# ATXDistributorBoard_ATM.net
KiCad netlist of a schematic drawn in EAGLE
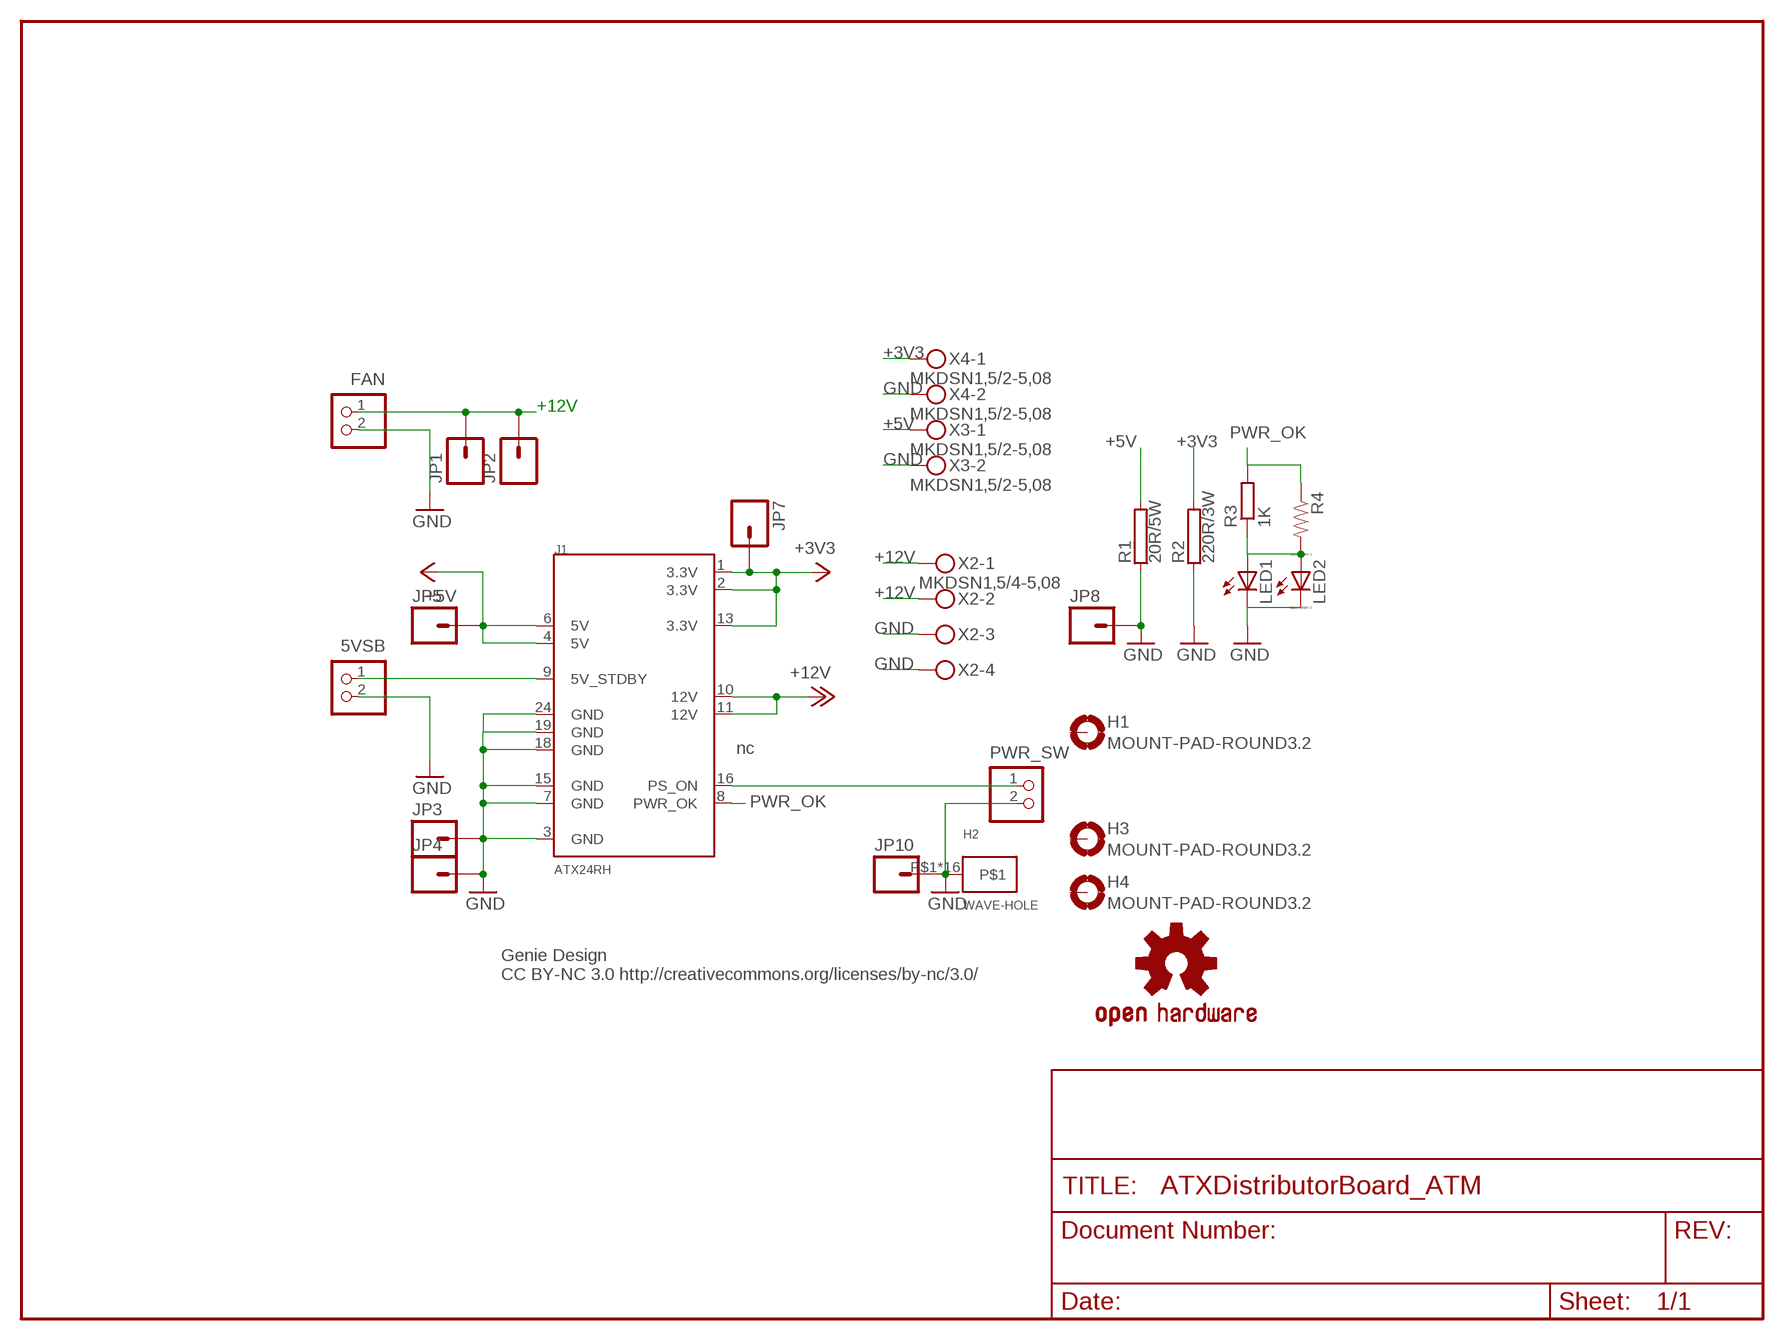
[diagram p0: schematic, sheet 1]

(export (version "E")
  (design (tool "Eeschema 10.0.6"))
  (components
    (comp (ref "5VSB")
      (value "B2B-XH-A")
      (footprint "eagle-import:B2B-XH-A")
      (libsource (lib "eagle-import") (part "B2B-XH-A"))
    )
    (comp (ref "FAN")
      (value "B2B-XH-A")
      (footprint "eagle-import:B2B-XH-A")
      (libsource (lib "eagle-import") (part "B2B-XH-A"))
    )
    (comp (ref "H1")
      (value "MOUNT-PAD-ROUND3.2")
      (footprint "eagle-import:3,2-PAD")
      (libsource (lib "eagle-import") (part "MOUNT-PAD-ROUND3.2"))
    )
    (comp (ref "H2")
      (value "WAVE-HOLE")
      (footprint "eagle-import:3,0-WAVE-HOLE")
      (libsource (lib "eagle-import") (part "WAVE-HOLE"))
    )
    (comp (ref "H3")
      (value "MOUNT-PAD-ROUND3.2")
      (footprint "eagle-import:3,2-PAD")
      (libsource (lib "eagle-import") (part "MOUNT-PAD-ROUND3.2"))
    )
    (comp (ref "H4")
      (value "MOUNT-PAD-ROUND3.2")
      (footprint "eagle-import:3,2-PAD")
      (libsource (lib "eagle-import") (part "MOUNT-PAD-ROUND3.2"))
    )
    (comp (ref "J1")
      (value "ATX24RH")
      (footprint "eagle-import:ATX24_RIGHT_ANGLE")
      (libsource (lib "eagle-import") (part "ATX24RH"))
    )
    (comp (ref "JP1")
      (value "M01PTH_NO_SILK_YES_STOP")
      (footprint "eagle-import:1X01_NO_SILK")
      (libsource (lib "eagle-import") (part "M01PTH_NO_SILK_YES_STOP"))
    )
    (comp (ref "JP2")
      (value "M01PTH_NO_SILK_YES_STOP")
      (footprint "eagle-import:1X01_NO_SILK")
      (libsource (lib "eagle-import") (part "M01PTH_NO_SILK_YES_STOP"))
    )
    (comp (ref "JP3")
      (value "M01PTH_NO_SILK_YES_STOP")
      (footprint "eagle-import:1X01_NO_SILK")
      (libsource (lib "eagle-import") (part "M01PTH_NO_SILK_YES_STOP"))
    )
    (comp (ref "JP4")
      (value "M01PTH_NO_SILK_YES_STOP")
      (footprint "eagle-import:1X01_NO_SILK")
      (libsource (lib "eagle-import") (part "M01PTH_NO_SILK_YES_STOP"))
    )
    (comp (ref "JP5")
      (value "M01PTH_NO_SILK_YES_STOP")
      (footprint "eagle-import:1X01_NO_SILK")
      (libsource (lib "eagle-import") (part "M01PTH_NO_SILK_YES_STOP"))
    )
    (comp (ref "JP7")
      (value "M01PTH_NO_SILK_YES_STOP")
      (footprint "eagle-import:1X01_NO_SILK")
      (libsource (lib "eagle-import") (part "M01PTH_NO_SILK_YES_STOP"))
    )
    (comp (ref "JP8")
      (value "M01PTH_NO_SILK_YES_STOP")
      (footprint "eagle-import:1X01_NO_SILK")
      (libsource (lib "eagle-import") (part "M01PTH_NO_SILK_YES_STOP"))
    )
    (comp (ref "JP10")
      (value "M01PTH_NO_SILK_YES_STOP")
      (footprint "eagle-import:1X01_NO_SILK")
      (libsource (lib "eagle-import") (part "M01PTH_NO_SILK_YES_STOP"))
    )
    (comp (ref "LED1")
      (value "LED3MM")
      (footprint "eagle-import:LED3MM")
      (libsource (lib "eagle-import") (part "LED3MM"))
    )
    (comp (ref "LED2")
      (value "LED_ESML0603")
      (footprint "eagle-import:LED_SML0603")
      (libsource (lib "eagle-import") (part "LED_ESML0603"))
    )
    (comp (ref "LOGO1")
      (value "OSHW-LOGOS-COPPER")
      (footprint "eagle-import:OSHW-LOGO-S_COPPER")
      (libsource (lib "eagle-import") (part "OSHW-LOGOS-COPPER"))
    )
    (comp (ref "PWR_SW")
      (value "B2B-XH-A")
      (footprint "eagle-import:B2B-XH-A")
      (libsource (lib "eagle-import") (part "B2B-XH-A"))
    )
    (comp (ref "R1")
      (value "20R/5W")
      (footprint "eagle-import:HPS923")
      (libsource (lib "eagle-import") (part "RHPS923"))
    )
    (comp (ref "R2")
      (value "220R/3W")
      (footprint "eagle-import:CA4050")
      (libsource (lib "eagle-import") (part "RCA4050"))
    )
    (comp (ref "R3")
      (value "1K")
      (footprint "eagle-import:0207_10")
      (libsource (lib "eagle-import") (part "R-EU_0207/10"))
    )
    (comp (ref "R4")
      (value "RESISTOR0603-RES")
      (footprint "eagle-import:0603-RES")
      (libsource (lib "eagle-import") (part "RESISTOR0603-RES"))
    )
    (comp (ref "X2")
      (value "MKDSN1,5/4-5,08")
      (footprint "eagle-import:MKDSN1,5_4-5,08")
      (fields (field (name "MPN") "SMKDSN1,5/4-5,08"))
      (libsource (lib "eagle-import") (part "MKDSN1,5/4-5,08"))
    )
    (comp (ref "X3")
      (value "MKDSN1,5/2-5,08")
      (footprint "eagle-import:MKDSN1,5_2-5,08")
      (fields (field (name "MPN") "MKDSN 1,5/2-5.08"))
      (libsource (lib "eagle-import") (part "MKDSN1,5/2-5,08"))
    )
    (comp (ref "X4")
      (value "MKDSN1,5/2-5,08")
      (footprint "eagle-import:MKDSN1,5_2-5,08")
      (fields (field (name "MPN") "MKDSN 1,5/2-5.08"))
      (libsource (lib "eagle-import") (part "MKDSN1,5/2-5,08"))
    )
  )
  (nets
    (net (code "1") (name "+3V3") (class "Default")
      (node (ref "J1") (pin "1") (pinfunction "3.3V_1") (pintype "bidirectional"))
      (node (ref "J1") (pin "13") (pinfunction "3.3V_13") (pintype "bidirectional"))
      (node (ref "J1") (pin "2") (pinfunction "3.3V_2") (pintype "bidirectional"))
      (node (ref "JP7") (pin "1") (pinfunction "1_1") (pintype "passive"))
      (node (ref "R2") (pin "2") (pinfunction "2_2") (pintype "passive"))
      (node (ref "X4") (pin "1") (pinfunction "KL_1") (pintype "passive"))
    )
    (net (code "2") (name "+5V") (class "Default")
      (node (ref "J1") (pin "4") (pinfunction "5V_4") (pintype "bidirectional"))
      (node (ref "J1") (pin "6") (pinfunction "5V_6") (pintype "bidirectional"))
      (node (ref "JP5") (pin "1") (pinfunction "1_1") (pintype "passive"))
      (node (ref "R1") (pin "2") (pinfunction "2_2") (pintype "passive"))
      (node (ref "X3") (pin "1") (pinfunction "KL_1") (pintype "passive"))
    )
    (net (code "3") (name "+12V") (class "Default")
      (node (ref "FAN") (pin "1") (pinfunction "1_1") (pintype "passive"))
      (node (ref "J1") (pin "10") (pinfunction "12V_10") (pintype "bidirectional"))
      (node (ref "J1") (pin "11") (pinfunction "12V_11") (pintype "bidirectional"))
      (node (ref "JP1") (pin "1") (pinfunction "1_1") (pintype "passive"))
      (node (ref "JP2") (pin "1") (pinfunction "1_1") (pintype "passive"))
      (node (ref "X2") (pin "1") (pinfunction "KL_1") (pintype "passive"))
      (node (ref "X2") (pin "2") (pinfunction "KL_2") (pintype "passive"))
    )
    (net (code "4") (name "/PWR_OK") (class "Default")
      (node (ref "J1") (pin "8") (pinfunction "PWR_OK_8") (pintype "bidirectional"))
      (node (ref "R3") (pin "2") (pinfunction "2_2") (pintype "passive"))
      (node (ref "R4") (pin "1") (pinfunction "1_1") (pintype "passive"))
    )
    (net (code "5") (name "GND") (class "Default")
      (node (ref "5VSB") (pin "2") (pinfunction "2_2") (pintype "passive"))
      (node (ref "FAN") (pin "2") (pinfunction "2_2") (pintype "passive"))
      (node (ref "H2") (pin "P$1") (pinfunction "P$1_P$1") (pintype "bidirectional"))
      (node (ref "H2") (pin "P$17") (pinfunction "P$1_P$17") (pintype "bidirectional"))
      (node (ref "H2") (pin "P$18") (pinfunction "P$1_P$18") (pintype "bidirectional"))
      (node (ref "H2") (pin "P$19") (pinfunction "P$1_P$19") (pintype "bidirectional"))
      (node (ref "H2") (pin "P$2") (pinfunction "P$1_P$2") (pintype "bidirectional"))
      (node (ref "H2") (pin "P$20") (pinfunction "P$1_P$20") (pintype "bidirectional"))
      (node (ref "H2") (pin "P$21") (pinfunction "P$1_P$21") (pintype "bidirectional"))
      (node (ref "H2") (pin "P$22") (pinfunction "P$1_P$22") (pintype "bidirectional"))
      (node (ref "H2") (pin "P$23") (pinfunction "P$1_P$23") (pintype "bidirectional"))
      (node (ref "H2") (pin "P$24") (pinfunction "P$1_P$24") (pintype "bidirectional"))
      (node (ref "H2") (pin "P$3") (pinfunction "P$1_P$3") (pintype "bidirectional"))
      (node (ref "H2") (pin "P$4") (pinfunction "P$1_P$4") (pintype "bidirectional"))
      (node (ref "H2") (pin "P$5") (pinfunction "P$1_P$5") (pintype "bidirectional"))
      (node (ref "H2") (pin "P$6") (pinfunction "P$1_P$6") (pintype "bidirectional"))
      (node (ref "H2") (pin "P$7") (pinfunction "P$1_P$7") (pintype "bidirectional"))
      (node (ref "H2") (pin "P$8") (pinfunction "P$1_P$8") (pintype "bidirectional"))
      (node (ref "J1") (pin "15") (pinfunction "GND_15") (pintype "bidirectional"))
      (node (ref "J1") (pin "18") (pinfunction "GND_18") (pintype "bidirectional"))
      (node (ref "J1") (pin "19") (pinfunction "GND_19") (pintype "bidirectional"))
      (node (ref "J1") (pin "24") (pinfunction "GND_24") (pintype "bidirectional"))
      (node (ref "J1") (pin "3") (pinfunction "GND_3") (pintype "bidirectional"))
      (node (ref "J1") (pin "7") (pinfunction "GND_7") (pintype "bidirectional"))
      (node (ref "JP10") (pin "1") (pinfunction "1_1") (pintype "passive"))
      (node (ref "JP3") (pin "1") (pinfunction "1_1") (pintype "passive"))
      (node (ref "JP4") (pin "1") (pinfunction "1_1") (pintype "passive"))
      (node (ref "JP8") (pin "1") (pinfunction "1_1") (pintype "passive"))
      (node (ref "LED1") (pin "K") (pinfunction "C_K") (pintype "passive"))
      (node (ref "LED2") (pin "C") (pinfunction "C_C") (pintype "passive"))
      (node (ref "PWR_SW") (pin "2") (pinfunction "2_2") (pintype "passive"))
      (node (ref "R1") (pin "1") (pinfunction "1_1") (pintype "passive"))
      (node (ref "R2") (pin "1") (pinfunction "1_1") (pintype "passive"))
      (node (ref "X2") (pin "3") (pinfunction "KL_3") (pintype "passive"))
      (node (ref "X2") (pin "4") (pinfunction "KL_4") (pintype "passive"))
      (node (ref "X3") (pin "2") (pinfunction "KL_2") (pintype "passive"))
      (node (ref "X4") (pin "2") (pinfunction "KL_2") (pintype "passive"))
    )
    (net (code "6") (name "Net-(J1-5V_STDBY)") (class "Default")
      (node (ref "5VSB") (pin "1") (pinfunction "1_1") (pintype "passive"))
      (node (ref "J1") (pin "9") (pinfunction "5V_STDBY_9") (pintype "bidirectional"))
    )
    (net (code "7") (name "Net-(J1-PS_ON)") (class "Default")
      (node (ref "J1") (pin "16") (pinfunction "PS_ON_16") (pintype "bidirectional"))
      (node (ref "PWR_SW") (pin "1") (pinfunction "1_1") (pintype "passive"))
    )
    (net (code "8") (name "Net-(LED1-PadA)") (class "Default")
      (node (ref "LED1") (pin "A") (pinfunction "A_A") (pintype "passive"))
      (node (ref "LED2") (pin "A") (pinfunction "A_A") (pintype "passive"))
      (node (ref "R3") (pin "1") (pinfunction "1_1") (pintype "passive"))
      (node (ref "R4") (pin "2") (pinfunction "2_2") (pintype "passive"))
    )
    (net (code "9") (name "unconnected-(H1-MOUNT-PadB3,2)") (class "Default")
      (node (ref "H1") (pin "B3,2") (pinfunction "MOUNT_B3,2") (pintype "passive"))
    )
    (net (code "10") (name "unconnected-(H3-MOUNT-PadB3,2)") (class "Default")
      (node (ref "H3") (pin "B3,2") (pinfunction "MOUNT_B3,2") (pintype "passive"))
    )
    (net (code "11") (name "unconnected-(H4-MOUNT-PadB3,2)") (class "Default")
      (node (ref "H4") (pin "B3,2") (pinfunction "MOUNT_B3,2") (pintype "passive"))
    )
  )
)
